# 24V_LM317.net
KiCad netlist of a schematic drawn in EAGLE
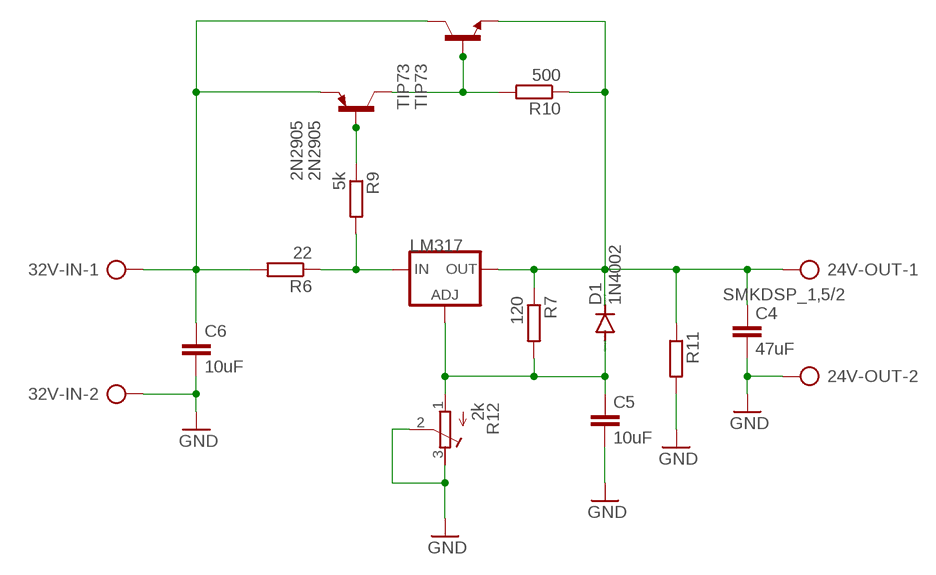
[diagram p0: schematic, sheet 1]

(export (version "E")
  (design (tool "Eeschema 10.0.6"))
  (components
    (comp (ref "2N2905")
      (value "2N2905")
      (footprint "eagle-import:TO39")
      (libsource (lib "eagle-import") (part "2N2905"))
    )
    (comp (ref "24V-OUT")
      (value "SMKDSP_1,5/2")
      (footprint "eagle-import:SMKDSP_1,5_2")
      (fields (field (name "MF") "FARNELL") (field (name "MPN") "1733570"))
      (libsource (lib "eagle-import") (part "SMKDSP_1,5/2"))
    )
    (comp (ref "32V-IN")
      (value "SMKDSP_1,5/2")
      (footprint "eagle-import:SMKDSP_1,5_2")
      (fields (field (name "MF") "FARNELL") (field (name "MPN") "1733570"))
      (libsource (lib "eagle-import") (part "SMKDSP_1,5/2"))
    )
    (comp (ref "C4")
      (value "47uF")
      (footprint "eagle-import:C025-025X050")
      (libsource (lib "eagle-import") (part "C-EU025-025X050"))
    )
    (comp (ref "C5")
      (value "10uF")
      (footprint "eagle-import:C025-025X050")
      (libsource (lib "eagle-import") (part "C-EU025-025X050"))
    )
    (comp (ref "C6")
      (value "10uF")
      (footprint "eagle-import:C025-025X050")
      (libsource (lib "eagle-import") (part "C-EU025-025X050"))
    )
    (comp (ref "D1")
      (value "1N4002")
      (footprint "eagle-import:DIOAD860W70L460D235B")
      (libsource (lib "eagle-import") (part "1N4004DO-41"))
    )
    (comp (ref "LM317")
      (value "LM317TS317TS_TO220")
      (footprint "eagle-import:TO220V")
      (libsource (lib "eagle-import") (part "LM317TS317TS_TO220"))
    )
    (comp (ref "R6")
      (value "22")
      (footprint "eagle-import:0204_7")
      (libsource (lib "eagle-import") (part "R-EU_0204/7"))
    )
    (comp (ref "R7")
      (value "120")
      (footprint "eagle-import:0204_7")
      (libsource (lib "eagle-import") (part "R-EU_0204/7"))
    )
    (comp (ref "R9")
      (value "5k")
      (footprint "eagle-import:0204_7")
      (libsource (lib "eagle-import") (part "R-EU_0204/7"))
    )
    (comp (ref "R10")
      (value "500")
      (footprint "eagle-import:0204_7")
      (libsource (lib "eagle-import") (part "R-EU_0204/7"))
    )
    (comp (ref "R11")
      (value "R-EU_0204/7")
      (footprint "eagle-import:0204_7")
      (libsource (lib "eagle-import") (part "R-EU_0204/7"))
    )
    (comp (ref "R12")
      (value "2k")
      (footprint "eagle-import:RTRIM64W")
      (libsource (lib "eagle-import") (part "R-TRIMM64W"))
    )
    (comp (ref "TIP73")
      (value "TIP73")
      (footprint "eagle-import:TO5")
      (libsource (lib "eagle-import") (part "2N1613"))
    )
  )
  (nets
    (net (code "1") (name "GND") (class "Default")
      (node (ref "24V-OUT") (pin "2") (pinfunction "KL_2") (pintype "passive"))
      (node (ref "32V-IN") (pin "2") (pinfunction "KL_2") (pintype "passive"))
      (node (ref "C4") (pin "2") (pinfunction "2_2") (pintype "passive"))
      (node (ref "C5") (pin "2") (pinfunction "2_2") (pintype "passive"))
      (node (ref "C6") (pin "2") (pinfunction "2_2") (pintype "passive"))
      (node (ref "R11") (pin "2") (pinfunction "2_2") (pintype "passive"))
      (node (ref "R12") (pin "2") (pinfunction "S_2") (pintype "passive"))
      (node (ref "R12") (pin "3") (pinfunction "E_3") (pintype "passive"))
    )
    (net (code "2") (name "Net-(2N2905-B)") (class "Default")
      (node (ref "2N2905") (pin "2") (pinfunction "B_2") (pintype "passive"))
      (node (ref "R9") (pin "1") (pinfunction "1_1") (pintype "passive"))
    )
    (net (code "3") (name "Net-(2N2905-C)") (class "Default")
      (node (ref "2N2905") (pin "3") (pinfunction "C_3") (pintype "passive"))
      (node (ref "R10") (pin "2") (pinfunction "2_2") (pintype "passive"))
      (node (ref "TIP73") (pin "2") (pinfunction "B_2") (pintype "passive"))
    )
    (net (code "4") (name "Net-(2N2905-E)") (class "Default")
      (node (ref "2N2905") (pin "1") (pinfunction "E_1") (pintype "passive"))
      (node (ref "32V-IN") (pin "1") (pinfunction "KL_1") (pintype "passive"))
      (node (ref "C6") (pin "1") (pinfunction "1_1") (pintype "passive"))
      (node (ref "R6") (pin "2") (pinfunction "2_2") (pintype "passive"))
      (node (ref "TIP73") (pin "3") (pinfunction "C_3") (pintype "passive"))
    )
    (net (code "5") (name "Net-(24V-OUTA-KL)") (class "Default")
      (node (ref "24V-OUT") (pin "1") (pinfunction "KL_1") (pintype "passive"))
      (node (ref "C4") (pin "1") (pinfunction "1_1") (pintype "passive"))
      (node (ref "D1") (pin "1") (pinfunction "C_1") (pintype "passive"))
      (node (ref "LM317") (pin "2") (pinfunction "OUT_2") (pintype "passive"))
      (node (ref "R10") (pin "1") (pinfunction "1_1") (pintype "passive"))
      (node (ref "R11") (pin "1") (pinfunction "1_1") (pintype "passive"))
      (node (ref "R7") (pin "1") (pinfunction "1_1") (pintype "passive"))
      (node (ref "TIP73") (pin "1") (pinfunction "E_1") (pintype "passive"))
    )
    (net (code "6") (name "Net-(D1-A)") (class "Default")
      (node (ref "C5") (pin "1") (pinfunction "1_1") (pintype "passive"))
      (node (ref "D1") (pin "2") (pinfunction "A_2") (pintype "passive"))
      (node (ref "LM317") (pin "1") (pinfunction "ADJ_1") (pintype "input"))
      (node (ref "R12") (pin "1") (pinfunction "A_1") (pintype "passive"))
      (node (ref "R7") (pin "2") (pinfunction "2_2") (pintype "passive"))
    )
    (net (code "7") (name "Net-(LM317-IN)") (class "Default")
      (node (ref "LM317") (pin "3") (pinfunction "IN_3") (pintype "input"))
      (node (ref "R6") (pin "1") (pinfunction "1_1") (pintype "passive"))
      (node (ref "R9") (pin "2") (pinfunction "2_2") (pintype "passive"))
    )
  )
)
